# RH007_1.net
KiCad netlist of a schematic drawn in EAGLE
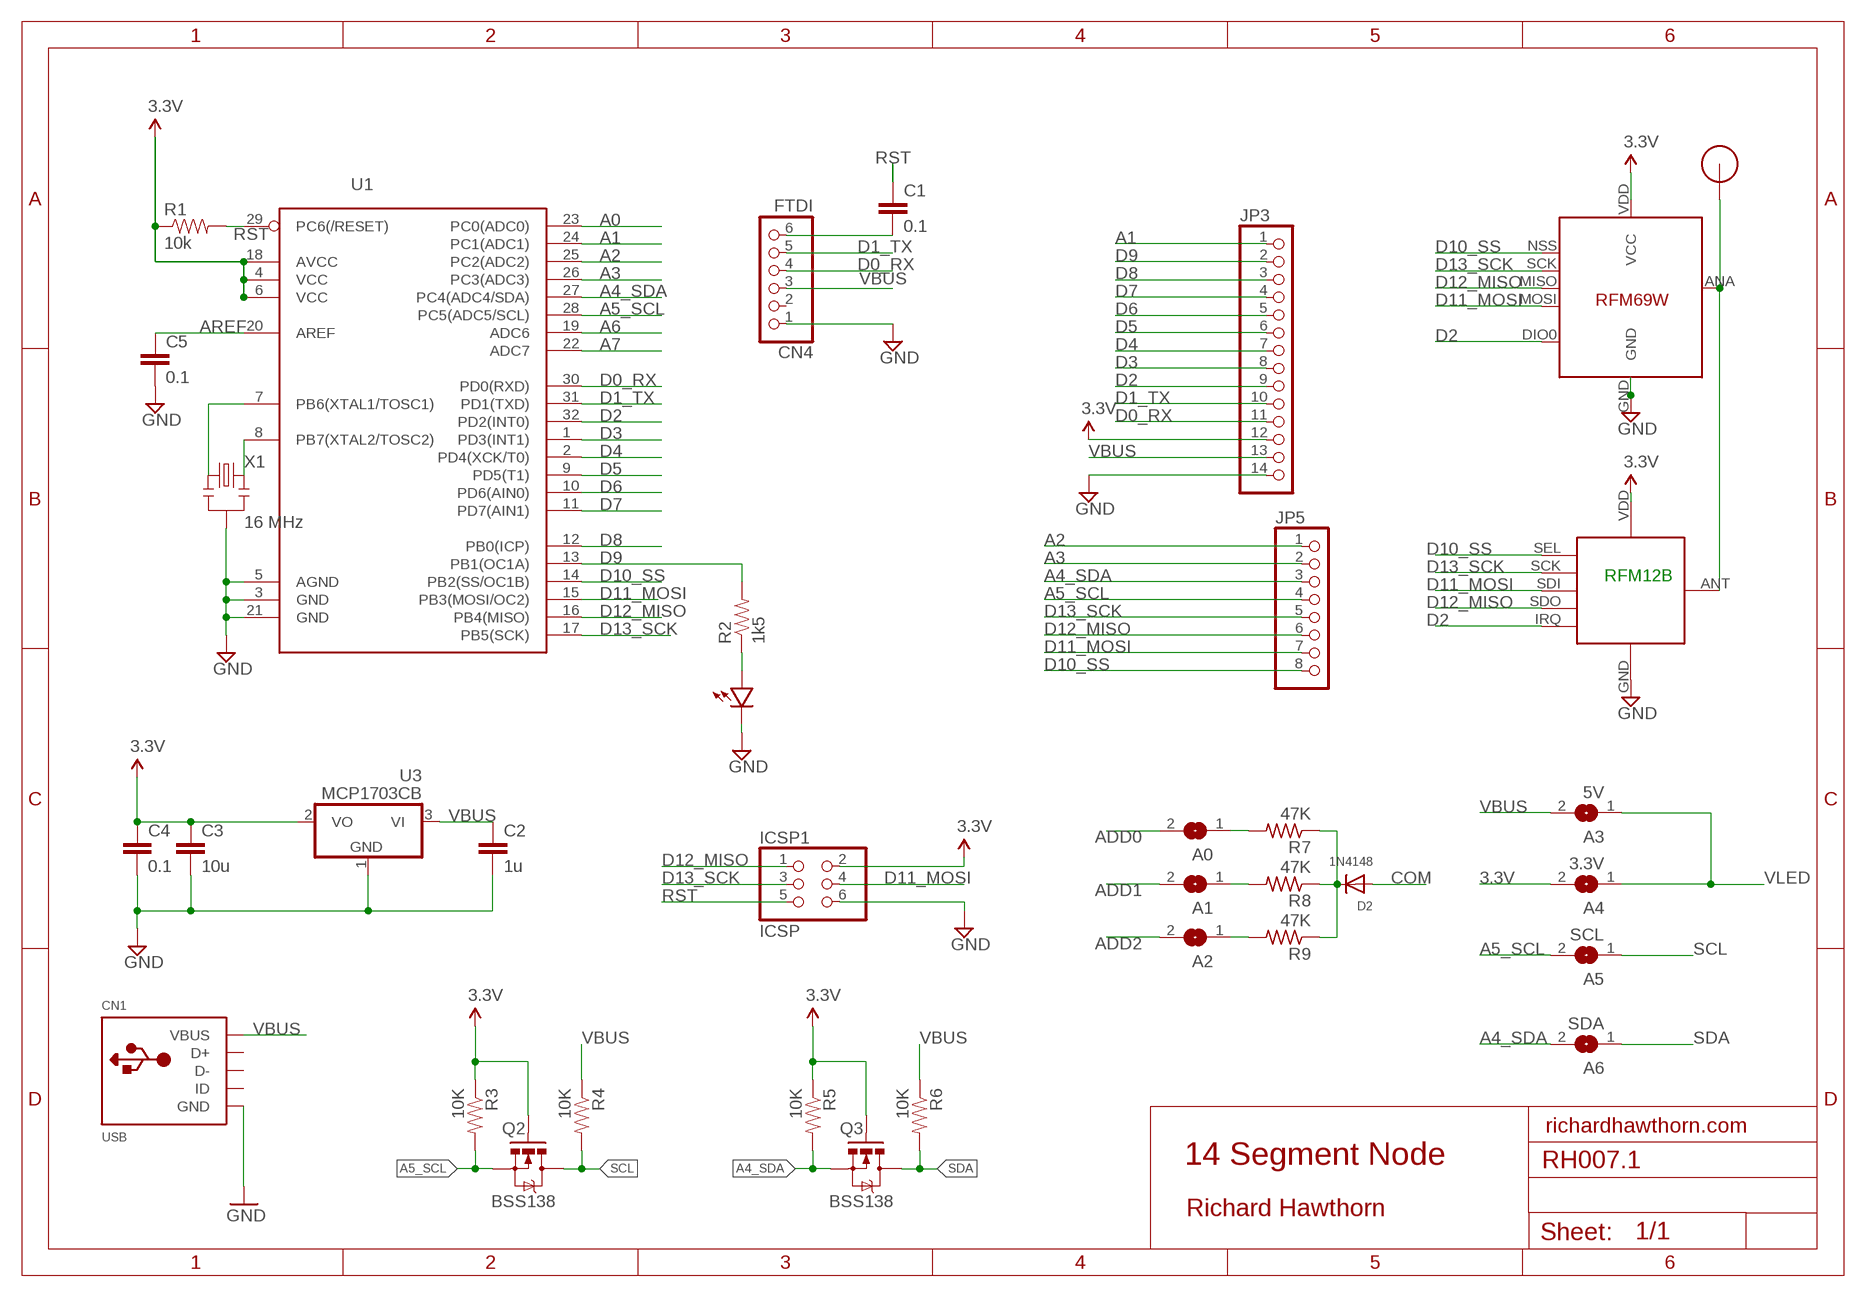
[diagram p0: schematic, sheet 1, part 1 of 2]
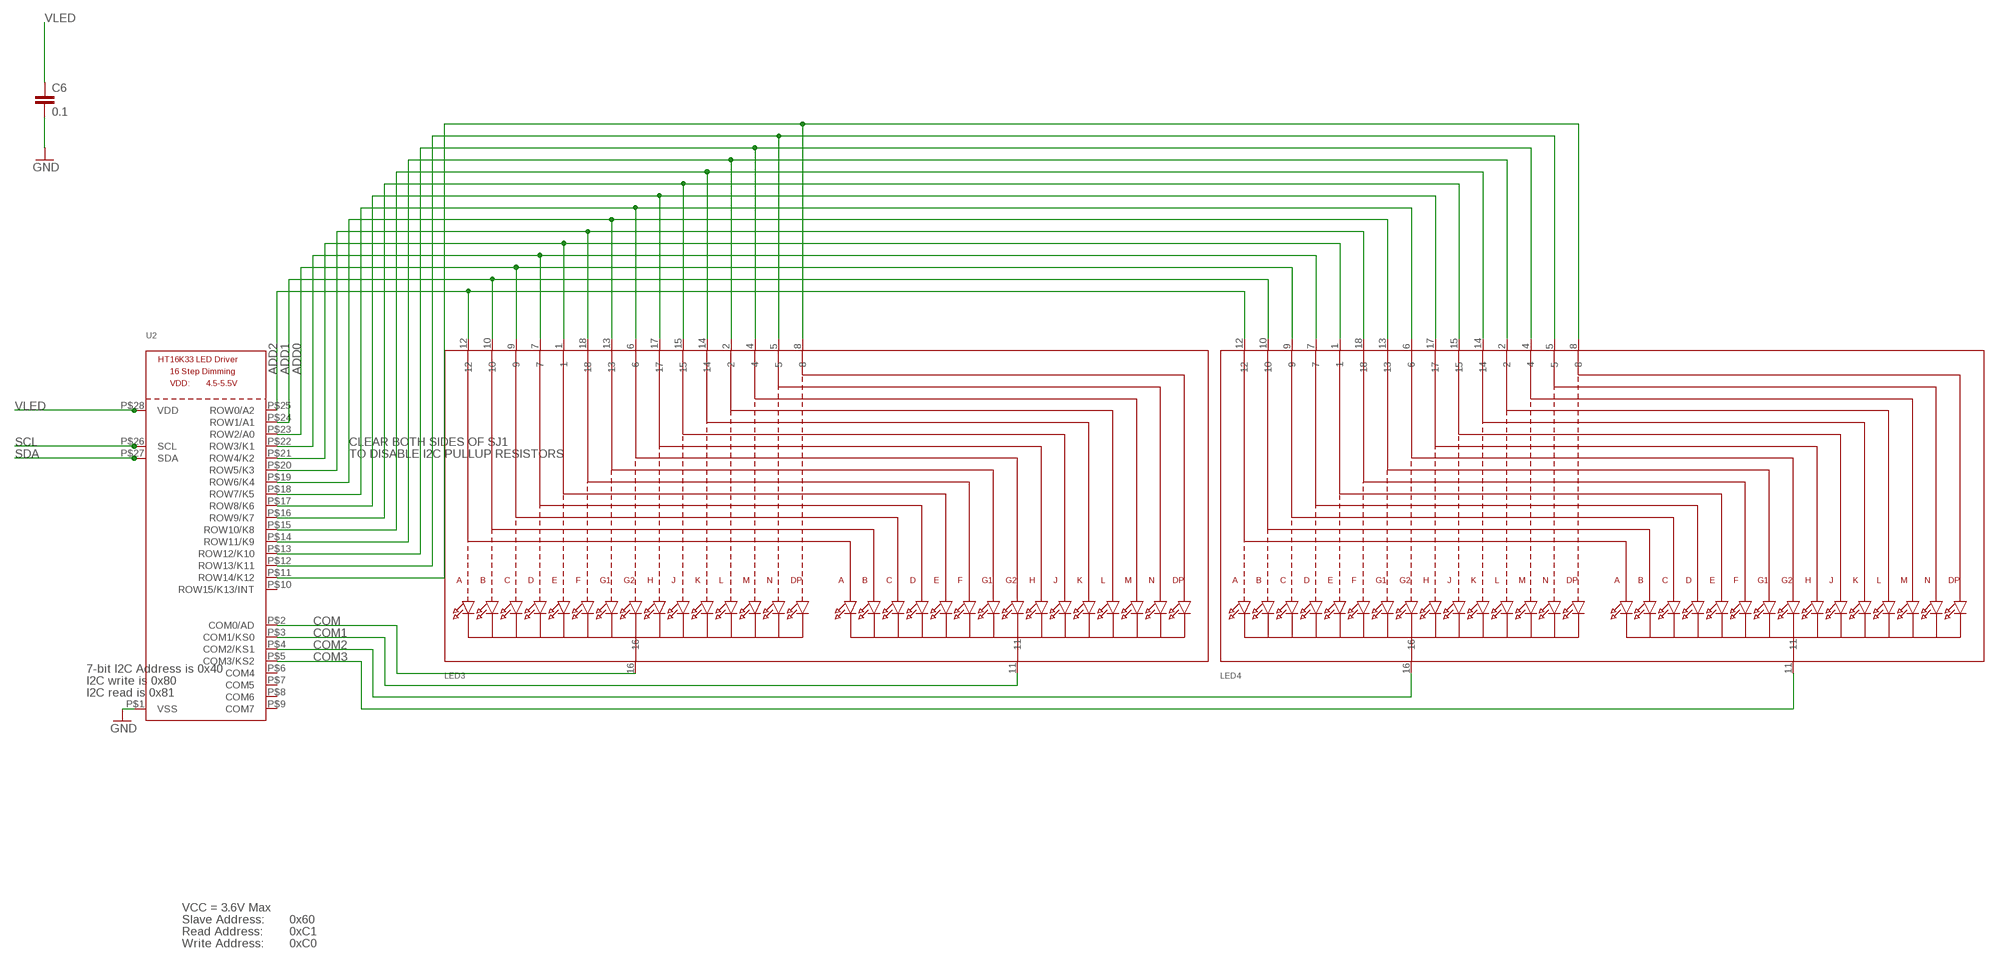
[diagram p1: schematic, sheet 1, part 2 of 2]

(export (version "E")
  (design (tool "Eeschema 10.0.6"))
  (components
    (comp (ref "A0")
      (value "SOLDERJUMPERREFLOW_NOPASTE")
      (footprint "eagle-import:SOLDERJUMPER_REFLOW_NOPASTE")
      (libsource (lib "eagle-import") (part "SOLDERJUMPERREFLOW_NOPASTE"))
    )
    (comp (ref "A1")
      (value "SOLDERJUMPERREFLOW_NOPASTE")
      (footprint "eagle-import:SOLDERJUMPER_REFLOW_NOPASTE")
      (libsource (lib "eagle-import") (part "SOLDERJUMPERREFLOW_NOPASTE"))
    )
    (comp (ref "A2")
      (value "SOLDERJUMPERREFLOW_NOPASTE")
      (footprint "eagle-import:SOLDERJUMPER_REFLOW_NOPASTE")
      (libsource (lib "eagle-import") (part "SOLDERJUMPERREFLOW_NOPASTE"))
    )
    (comp (ref "A3")
      (value "5V")
      (footprint "eagle-import:SOLDERJUMPER_REFLOW_NOPASTE")
      (libsource (lib "eagle-import") (part "SOLDERJUMPERREFLOW_NOPASTE"))
    )
    (comp (ref "A4")
      (value "3.3V")
      (footprint "eagle-import:SOLDERJUMPER_REFLOW_NOPASTE")
      (libsource (lib "eagle-import") (part "SOLDERJUMPERREFLOW_NOPASTE"))
    )
    (comp (ref "A5")
      (value "SCL")
      (footprint "eagle-import:SOLDERJUMPER_REFLOW_NOPASTE")
      (libsource (lib "eagle-import") (part "SOLDERJUMPERREFLOW_NOPASTE"))
    )
    (comp (ref "A6")
      (value "SDA")
      (footprint "eagle-import:SOLDERJUMPER_REFLOW_NOPASTE")
      (libsource (lib "eagle-import") (part "SOLDERJUMPERREFLOW_NOPASTE"))
    )
    (comp (ref "C1")
      (value "0.1")
      (footprint "eagle-import:0603-CAP")
      (libsource (lib "eagle-import") (part "CAP0603-CAP"))
    )
    (comp (ref "C2")
      (value "1u")
      (footprint "eagle-import:0603-CAP")
      (libsource (lib "eagle-import") (part "CAP0603-CAP"))
    )
    (comp (ref "C3")
      (value "10u")
      (footprint "eagle-import:0805-CAP")
      (libsource (lib "eagle-import") (part "CAP0805-CAP"))
    )
    (comp (ref "C4")
      (value "0.1")
      (footprint "eagle-import:0603-CAP")
      (libsource (lib "eagle-import") (part "CAP0603-CAP"))
    )
    (comp (ref "C5")
      (value "0.1")
      (footprint "eagle-import:0603-CAP")
      (libsource (lib "eagle-import") (part "CAP0603-CAP"))
    )
    (comp (ref "C6")
      (value "0.1")
      (footprint "eagle-import:0603-CAP")
      (libsource (lib "eagle-import") (part "CAP0603-CAP"))
    )
    (comp (ref "CN1")
      (value "USB")
      (footprint "eagle-import:USB-MINIB")
      (libsource (lib "eagle-import") (part "USBMINIB"))
    )
    (comp (ref "CN4")
      (value "FTDI")
      (footprint "eagle-import:1X06")
      (libsource (lib "eagle-import") (part "PINHD-1X6"))
    )
    (comp (ref "D2")
      (value "1N4148")
      (footprint "eagle-import:SOD-323F")
      (libsource (lib "eagle-import") (part "DIODESOD-323F"))
    )
    (comp (ref "ICSP1")
      (value "ICSP")
      (footprint "eagle-import:2X03")
      (libsource (lib "eagle-import") (part "PINHD-2X3"))
    )
    (comp (ref "JP3")
      (value "PINHD-1X14")
      (footprint "eagle-import:1X14")
      (libsource (lib "eagle-import") (part "PINHD-1X14"))
    )
    (comp (ref "JP5")
      (value "PINHD-1X8")
      (footprint "eagle-import:1X08")
      (libsource (lib "eagle-import") (part "PINHD-1X8"))
    )
    (comp (ref "LED1")
      (value "LED0603")
      (footprint "eagle-import:0603-LED")
      (libsource (lib "eagle-import") (part "LED0603"))
    )
    (comp (ref "LED3")
      (value "DISP_SEGMENT_STARBURST_DUAL_COMMONCATHODE")
      (footprint "eagle-import:SEGMENT_STARTBUST_DUAL_KWA-541CBB")
      (libsource (lib "eagle-import") (part "DISP_SEGMENT_STARBURST_DUAL_COMMONCATHODE"))
    )
    (comp (ref "LED4")
      (value "DISP_SEGMENT_STARBURST_DUAL_COMMONCATHODE")
      (footprint "eagle-import:SEGMENT_STARTBUST_DUAL_KWA-541CBB")
      (libsource (lib "eagle-import") (part "DISP_SEGMENT_STARBURST_DUAL_COMMONCATHODE"))
    )
    (comp (ref "Q2")
      (value "BSS138")
      (footprint "eagle-import:SOT23-3")
      (libsource (lib "eagle-import") (part "MOSFET-NCHANNELSMD"))
    )
    (comp (ref "Q3")
      (value "BSS138")
      (footprint "eagle-import:SOT23-3")
      (libsource (lib "eagle-import") (part "MOSFET-NCHANNELSMD"))
    )
    (comp (ref "R1")
      (value "10k")
      (footprint "eagle-import:0603-RES")
      (libsource (lib "eagle-import") (part "RESISTOR0603-RES"))
    )
    (comp (ref "R2")
      (value "1k5")
      (footprint "eagle-import:0805")
      (libsource (lib "eagle-import") (part "RESISTOR0805"))
    )
    (comp (ref "R3")
      (value "10K")
      (footprint "eagle-import:0603-RES")
      (libsource (lib "eagle-import") (part "SparkFun_RESISTOR0603-RES"))
    )
    (comp (ref "R4")
      (value "10K")
      (footprint "eagle-import:0603-RES")
      (libsource (lib "eagle-import") (part "SparkFun_RESISTOR0603-RES"))
    )
    (comp (ref "R5")
      (value "10K")
      (footprint "eagle-import:0603-RES")
      (libsource (lib "eagle-import") (part "SparkFun_RESISTOR0603-RES"))
    )
    (comp (ref "R6")
      (value "10K")
      (footprint "eagle-import:0603-RES")
      (libsource (lib "eagle-import") (part "SparkFun_RESISTOR0603-RES"))
    )
    (comp (ref "R7")
      (value "47K")
      (footprint "eagle-import:R0805")
      (libsource (lib "eagle-import") (part "R-US_R0805"))
    )
    (comp (ref "R8")
      (value "47K")
      (footprint "eagle-import:R0805")
      (libsource (lib "eagle-import") (part "R-US_R0805"))
    )
    (comp (ref "R9")
      (value "47K")
      (footprint "eagle-import:R0805")
      (libsource (lib "eagle-import") (part "R-US_R0805"))
    )
    (comp (ref "RF1")
      (value "RFM12B")
      (footprint "eagle-import:RFM12B-MINPADS")
      (libsource (lib "eagle-import") (part "RFM12B_MINPADS"))
    )
    (comp (ref "RF2")
      (value "RFM69")
      (footprint "eagle-import:RFM69W-MINPADS")
      (libsource (lib "eagle-import") (part "RFM69"))
    )
    (comp (ref "U$1")
      (value "RFM12B_ANTENNA")
      (footprint "eagle-import:RFM12B-ANTENNA")
      (libsource (lib "eagle-import") (part "RFM12B_ANTENNA"))
    )
    (comp (ref "U1")
      (value "ATMega-328")
      (footprint "eagle-import:TQFP32-08")
      (libsource (lib "eagle-import") (part "ATMEGA168/328TQFP32"))
    )
    (comp (ref "U2")
      (value "HT16K33_SOP28")
      (footprint "eagle-import:SOP28_300MIL")
      (libsource (lib "eagle-import") (part "HT16K33_SOP28"))
    )
    (comp (ref "U3")
      (value "MCP1703CB")
      (footprint "eagle-import:SOT23")
      (libsource (lib "eagle-import") (part "MCP1703CB"))
    )
    (comp (ref "X1")
      (value "16 MHz")
      (footprint "eagle-import:RESONATOR-SMD")
      (libsource (lib "eagle-import") (part "RESONATORSMD"))
    )
  )
  (nets
    (net (code "1") (name "/A0") (class "Default")
      (node (ref "U1") (pin "23") (pinfunction "PC0(ADC0)_23") (pintype "bidirectional"))
    )
    (net (code "2") (name "/A1") (class "Default")
      (node (ref "JP3") (pin "1") (pinfunction "1_1") (pintype "passive"))
      (node (ref "U1") (pin "24") (pinfunction "PC1(ADC1)_24") (pintype "bidirectional"))
    )
    (net (code "3") (name "/A2") (class "Default")
      (node (ref "JP5") (pin "1") (pinfunction "1_1") (pintype "passive"))
      (node (ref "U1") (pin "25") (pinfunction "PC2(ADC2)_25") (pintype "bidirectional"))
    )
    (net (code "4") (name "/A3") (class "Default")
      (node (ref "JP5") (pin "2") (pinfunction "2_2") (pintype "passive"))
      (node (ref "U1") (pin "26") (pinfunction "PC3(ADC3)_26") (pintype "bidirectional"))
    )
    (net (code "5") (name "/A6") (class "Default")
      (node (ref "U1") (pin "19") (pinfunction "ADC6_19") (pintype "bidirectional"))
    )
    (net (code "6") (name "/A7") (class "Default")
      (node (ref "U1") (pin "22") (pinfunction "ADC7_22") (pintype "bidirectional"))
    )
    (net (code "7") (name "/ADD0") (class "Default")
      (node (ref "A0") (pin "2") (pinfunction "2_2") (pintype "passive"))
      (node (ref "LED3") (pin "9") (pinfunction "9_9") (pintype "bidirectional"))
      (node (ref "LED4") (pin "9") (pinfunction "9_9") (pintype "bidirectional"))
      (node (ref "U2") (pin "P$23") (pinfunction "ROW2/A0_P$23") (pintype "bidirectional"))
    )
    (net (code "8") (name "/ADD1") (class "Default")
      (node (ref "A1") (pin "2") (pinfunction "2_2") (pintype "passive"))
      (node (ref "LED3") (pin "10") (pinfunction "10_10") (pintype "bidirectional"))
      (node (ref "LED4") (pin "10") (pinfunction "10_10") (pintype "bidirectional"))
      (node (ref "U2") (pin "P$24") (pinfunction "ROW1/A1_P$24") (pintype "bidirectional"))
    )
    (net (code "9") (name "/ADD2") (class "Default")
      (node (ref "A2") (pin "2") (pinfunction "2_2") (pintype "passive"))
      (node (ref "LED3") (pin "12") (pinfunction "12_12") (pintype "bidirectional"))
      (node (ref "LED4") (pin "12") (pinfunction "12_12") (pintype "bidirectional"))
      (node (ref "U2") (pin "P$25") (pinfunction "ROW0/A2_P$25") (pintype "bidirectional"))
    )
    (net (code "10") (name "/AREF") (class "Default")
      (node (ref "C5") (pin "1") (pinfunction "1_1") (pintype "passive"))
      (node (ref "U1") (pin "20") (pinfunction "AREF_20") (pintype "bidirectional"))
    )
    (net (code "11") (name "/COM") (class "Default")
      (node (ref "D2") (pin "A") (pinfunction "A_A") (pintype "passive"))
      (node (ref "LED3") (pin "16") (pinfunction "16_16") (pintype "bidirectional"))
      (node (ref "U2") (pin "P$2") (pinfunction "COM0/AD_P$2") (pintype "bidirectional"))
    )
    (net (code "12") (name "/COM1") (class "Default")
      (node (ref "LED3") (pin "11") (pinfunction "11_11") (pintype "bidirectional"))
      (node (ref "U2") (pin "P$3") (pinfunction "COM1/KS0_P$3") (pintype "bidirectional"))
    )
    (net (code "13") (name "/COM2") (class "Default")
      (node (ref "LED4") (pin "16") (pinfunction "16_16") (pintype "bidirectional"))
      (node (ref "U2") (pin "P$4") (pinfunction "COM2/KS1_P$4") (pintype "bidirectional"))
    )
    (net (code "14") (name "/COM3") (class "Default")
      (node (ref "LED4") (pin "11") (pinfunction "11_11") (pintype "bidirectional"))
      (node (ref "U2") (pin "P$5") (pinfunction "COM3/KS2_P$5") (pintype "bidirectional"))
    )
    (net (code "15") (name "/D0_RX") (class "Default")
      (node (ref "CN4") (pin "4") (pinfunction "4_4") (pintype "passive"))
      (node (ref "JP3") (pin "11") (pinfunction "11_11") (pintype "passive"))
      (node (ref "U1") (pin "30") (pinfunction "PD0(RXD)_30") (pintype "bidirectional"))
    )
    (net (code "16") (name "/D1_TX") (class "Default")
      (node (ref "CN4") (pin "5") (pinfunction "5_5") (pintype "passive"))
      (node (ref "JP3") (pin "10") (pinfunction "10_10") (pintype "passive"))
      (node (ref "U1") (pin "31") (pinfunction "PD1(TXD)_31") (pintype "bidirectional"))
    )
    (net (code "17") (name "/D2") (class "Default")
      (node (ref "JP3") (pin "9") (pinfunction "9_9") (pintype "passive"))
      (node (ref "RF1") (pin "IRQ") (pinfunction "IRQ_IRQ") (pintype "bidirectional"))
      (node (ref "RF2") (pin "DIO0") (pinfunction "DIO0_DIO0") (pintype "open_collector"))
      (node (ref "U1") (pin "32") (pinfunction "PD2(INT0)_32") (pintype "bidirectional"))
    )
    (net (code "18") (name "/D3") (class "Default")
      (node (ref "JP3") (pin "8") (pinfunction "8_8") (pintype "passive"))
      (node (ref "U1") (pin "1") (pinfunction "PD3(INT1)_1") (pintype "bidirectional"))
    )
    (net (code "19") (name "/D4") (class "Default")
      (node (ref "JP3") (pin "7") (pinfunction "7_7") (pintype "passive"))
      (node (ref "U1") (pin "2") (pinfunction "PD4(XCK/T0)_2") (pintype "bidirectional"))
    )
    (net (code "20") (name "/D5") (class "Default")
      (node (ref "JP3") (pin "6") (pinfunction "6_6") (pintype "passive"))
      (node (ref "U1") (pin "9") (pinfunction "PD5(T1)_9") (pintype "bidirectional"))
    )
    (net (code "21") (name "/D6") (class "Default")
      (node (ref "JP3") (pin "5") (pinfunction "5_5") (pintype "passive"))
      (node (ref "U1") (pin "10") (pinfunction "PD6(AIN0)_10") (pintype "bidirectional"))
    )
    (net (code "22") (name "/D7") (class "Default")
      (node (ref "JP3") (pin "4") (pinfunction "4_4") (pintype "passive"))
      (node (ref "U1") (pin "11") (pinfunction "PD7(AIN1)_11") (pintype "bidirectional"))
    )
    (net (code "23") (name "/D8") (class "Default")
      (node (ref "JP3") (pin "3") (pinfunction "3_3") (pintype "passive"))
      (node (ref "U1") (pin "12") (pinfunction "PB0(ICP)_12") (pintype "bidirectional"))
    )
    (net (code "24") (name "/D9") (class "Default")
      (node (ref "JP3") (pin "2") (pinfunction "2_2") (pintype "passive"))
      (node (ref "R2") (pin "2") (pinfunction "2_2") (pintype "passive"))
      (node (ref "U1") (pin "13") (pinfunction "PB1(OC1A)_13") (pintype "bidirectional"))
    )
    (net (code "25") (name "/D10_SS") (class "Default")
      (node (ref "JP5") (pin "8") (pinfunction "8_8") (pintype "passive"))
      (node (ref "RF1") (pin "SEL") (pinfunction "SEL_SEL") (pintype "bidirectional"))
      (node (ref "RF2") (pin "NSS") (pinfunction "SEL_NSS") (pintype "input"))
      (node (ref "U1") (pin "14") (pinfunction "PB2(SS/OC1B)_14") (pintype "bidirectional"))
    )
    (net (code "26") (name "/D11_MOSI") (class "Default")
      (node (ref "ICSP1") (pin "4") (pinfunction "4_4") (pintype "passive"))
      (node (ref "JP5") (pin "7") (pinfunction "7_7") (pintype "passive"))
      (node (ref "RF1") (pin "SDI") (pinfunction "SDI/MOSI_SDI") (pintype "bidirectional"))
      (node (ref "RF2") (pin "MOSI") (pinfunction "MOSI_MOSI") (pintype "output"))
      (node (ref "U1") (pin "15") (pinfunction "PB3(MOSI/OC2)_15") (pintype "bidirectional"))
    )
    (net (code "27") (name "/D12_MISO") (class "Default")
      (node (ref "ICSP1") (pin "1") (pinfunction "1_1") (pintype "passive"))
      (node (ref "JP5") (pin "6") (pinfunction "6_6") (pintype "passive"))
      (node (ref "RF1") (pin "SDO") (pinfunction "SDO/MISO_SDO") (pintype "bidirectional"))
      (node (ref "RF2") (pin "MISO") (pinfunction "MISO_MISO") (pintype "input"))
      (node (ref "U1") (pin "16") (pinfunction "PB4(MISO)_16") (pintype "bidirectional"))
    )
    (net (code "28") (name "/D13_SCK") (class "Default")
      (node (ref "ICSP1") (pin "3") (pinfunction "3_3") (pintype "passive"))
      (node (ref "JP5") (pin "5") (pinfunction "5_5") (pintype "passive"))
      (node (ref "RF1") (pin "SCK") (pinfunction "SCK_SCK") (pintype "bidirectional"))
      (node (ref "RF2") (pin "SCK") (pinfunction "SCK_SCK") (pintype "input"))
      (node (ref "U1") (pin "17") (pinfunction "PB5(SCK)_17") (pintype "bidirectional"))
    )
    (net (code "29") (name "/RST") (class "Default")
      (node (ref "C1") (pin "1") (pinfunction "1_1") (pintype "passive"))
      (node (ref "ICSP1") (pin "5") (pinfunction "5_5") (pintype "passive"))
      (node (ref "R1") (pin "2") (pinfunction "2_2") (pintype "passive"))
      (node (ref "U1") (pin "29") (pinfunction "PC6(/RESET)_29") (pintype "bidirectional"))
    )
    (net (code "30") (name "/VBUS") (class "Default")
      (node (ref "A3") (pin "2") (pinfunction "2_2") (pintype "passive"))
      (node (ref "C2") (pin "1") (pinfunction "1_1") (pintype "passive"))
      (node (ref "CN1") (pin "VBUS") (pinfunction "VBUS_VBUS") (pintype "power_in"))
      (node (ref "CN4") (pin "3") (pinfunction "3_3") (pintype "passive"))
      (node (ref "JP3") (pin "13") (pinfunction "13_13") (pintype "passive"))
      (node (ref "R4") (pin "1") (pinfunction "1_1") (pintype "passive"))
      (node (ref "R6") (pin "1") (pinfunction "1_1") (pintype "passive"))
      (node (ref "U3") (pin "3") (pinfunction "VI_3") (pintype "input"))
    )
    (net (code "31") (name "/VLED") (class "Default")
      (node (ref "A3") (pin "1") (pinfunction "1_1") (pintype "passive"))
      (node (ref "A4") (pin "1") (pinfunction "1_1") (pintype "passive"))
      (node (ref "C6") (pin "1") (pinfunction "1_1") (pintype "passive"))
      (node (ref "U2") (pin "P$28") (pinfunction "VDD_P$28") (pintype "bidirectional"))
    )
    (net (code "32") (name "3.3V") (class "Default")
      (node (ref "A4") (pin "2") (pinfunction "2_2") (pintype "passive"))
      (node (ref "C3") (pin "1") (pinfunction "1_1") (pintype "passive"))
      (node (ref "C4") (pin "1") (pinfunction "1_1") (pintype "passive"))
      (node (ref "ICSP1") (pin "2") (pinfunction "2_2") (pintype "passive"))
      (node (ref "JP3") (pin "12") (pinfunction "12_12") (pintype "passive"))
      (node (ref "Q2") (pin "1") (pinfunction "G_1") (pintype "passive"))
      (node (ref "Q3") (pin "1") (pinfunction "G_1") (pintype "passive"))
      (node (ref "R1") (pin "1") (pinfunction "1_1") (pintype "passive"))
      (node (ref "R3") (pin "1") (pinfunction "1_1") (pintype "passive"))
      (node (ref "R5") (pin "1") (pinfunction "1_1") (pintype "passive"))
      (node (ref "RF1") (pin "VDD") (pinfunction "VDD_VDD") (pintype "bidirectional"))
      (node (ref "RF2") (pin "VDD") (pinfunction "VCC_VDD") (pintype "power_in"))
      (node (ref "U1") (pin "18") (pinfunction "AVCC_18") (pintype "bidirectional"))
      (node (ref "U1") (pin "4") (pinfunction "VCC_4") (pintype "bidirectional"))
      (node (ref "U1") (pin "6") (pinfunction "VCC_6") (pintype "bidirectional"))
      (node (ref "U3") (pin "2") (pinfunction "VO_2") (pintype "passive"))
    )
    (net (code "33") (name "A4_SDA") (class "Default")
      (node (ref "A6") (pin "2") (pinfunction "2_2") (pintype "passive"))
      (node (ref "JP5") (pin "3") (pinfunction "3_3") (pintype "passive"))
      (node (ref "Q3") (pin "2") (pinfunction "S_2") (pintype "passive"))
      (node (ref "R5") (pin "2") (pinfunction "2_2") (pintype "passive"))
      (node (ref "U1") (pin "27") (pinfunction "PC4(ADC4/SDA)_27") (pintype "bidirectional"))
    )
    (net (code "34") (name "A5_SCL") (class "Default")
      (node (ref "A5") (pin "2") (pinfunction "2_2") (pintype "passive"))
      (node (ref "JP5") (pin "4") (pinfunction "4_4") (pintype "passive"))
      (node (ref "Q2") (pin "2") (pinfunction "S_2") (pintype "passive"))
      (node (ref "R3") (pin "2") (pinfunction "2_2") (pintype "passive"))
      (node (ref "U1") (pin "28") (pinfunction "PC5(ADC5/SCL)_28") (pintype "bidirectional"))
    )
    (net (code "35") (name "GND") (class "Default")
      (node (ref "C2") (pin "2") (pinfunction "2_2") (pintype "passive"))
      (node (ref "C3") (pin "2") (pinfunction "2_2") (pintype "passive"))
      (node (ref "C4") (pin "2") (pinfunction "2_2") (pintype "passive"))
      (node (ref "C5") (pin "2") (pinfunction "2_2") (pintype "passive"))
      (node (ref "C6") (pin "2") (pinfunction "2_2") (pintype "passive"))
      (node (ref "CN1") (pin "GND") (pinfunction "GND_GND") (pintype "power_in"))
      (node (ref "CN4") (pin "1") (pinfunction "1_1") (pintype "passive"))
      (node (ref "ICSP1") (pin "6") (pinfunction "6_6") (pintype "passive"))
      (node (ref "JP3") (pin "14") (pinfunction "14_14") (pintype "passive"))
      (node (ref "LED1") (pin "MINUS") (pinfunction "MINUS_MINUS") (pintype "passive"))
      (node (ref "RF1") (pin "GND") (pinfunction "GND_GND") (pintype "bidirectional"))
      (node (ref "RF2") (pin "GND") (pinfunction "GND_GND") (pintype "power_in"))
      (node (ref "U1") (pin "21") (pinfunction "GND_21") (pintype "bidirectional"))
      (node (ref "U1") (pin "3") (pinfunction "GND_3") (pintype "bidirectional"))
      (node (ref "U1") (pin "5") (pinfunction "AGND_5") (pintype "bidirectional"))
      (node (ref "U2") (pin "P$1") (pinfunction "VSS_P$1") (pintype "bidirectional"))
      (node (ref "U3") (pin "1") (pinfunction "GND_1") (pintype "passive"))
      (node (ref "X1") (pin "2") (pinfunction "2_2") (pintype "passive"))
    )
    (net (code "36") (name "Net-(A0-Pad1)") (class "Default")
      (node (ref "A0") (pin "1") (pinfunction "1_1") (pintype "passive"))
      (node (ref "R7") (pin "2") (pinfunction "2_2") (pintype "passive"))
    )
    (net (code "37") (name "Net-(A1-Pad1)") (class "Default")
      (node (ref "A1") (pin "1") (pinfunction "1_1") (pintype "passive"))
      (node (ref "R8") (pin "2") (pinfunction "2_2") (pintype "passive"))
    )
    (net (code "38") (name "Net-(A2-Pad1)") (class "Default")
      (node (ref "A2") (pin "1") (pinfunction "1_1") (pintype "passive"))
      (node (ref "R9") (pin "2") (pinfunction "2_2") (pintype "passive"))
    )
    (net (code "39") (name "Net-(C1-Pad2)") (class "Default")
      (node (ref "C1") (pin "2") (pinfunction "2_2") (pintype "passive"))
      (node (ref "CN4") (pin "6") (pinfunction "6_6") (pintype "passive"))
    )
    (net (code "40") (name "Net-(D2-PadC)") (class "Default")
      (node (ref "D2") (pin "C") (pinfunction "C_C") (pintype "passive"))
      (node (ref "R7") (pin "1") (pinfunction "1_1") (pintype "passive"))
      (node (ref "R8") (pin "1") (pinfunction "1_1") (pintype "passive"))
      (node (ref "R9") (pin "1") (pinfunction "1_1") (pintype "passive"))
    )
    (net (code "41") (name "Net-(LED1-PadPLUS)") (class "Default")
      (node (ref "LED1") (pin "PLUS") (pinfunction "PLUS_PLUS") (pintype "passive"))
      (node (ref "R2") (pin "1") (pinfunction "1_1") (pintype "passive"))
    )
    (net (code "42") (name "Net-(RF2-ANT)") (class "Default")
      (node (ref "RF1") (pin "ANT") (pinfunction "ANT_ANT") (pintype "bidirectional"))
      (node (ref "RF2") (pin "ANA") (pinfunction "ANT_ANA") (pintype "passive"))
      (node (ref "U$1") (pin "P$1") (pinfunction "1_P$1") (pintype "bidirectional"))
    )
    (net (code "43") (name "Net-(U1-PB6(XTAL1{slash}TOSC1))") (class "Default")
      (node (ref "U1") (pin "7") (pinfunction "PB6(XTAL1/TOSC1)_7") (pintype "bidirectional"))
      (node (ref "X1") (pin "1") (pinfunction "1_1") (pintype "passive"))
    )
    (net (code "44") (name "Net-(U1-PB7(XTAL2{slash}TOSC2))") (class "Default")
      (node (ref "U1") (pin "8") (pinfunction "PB7(XTAL2/TOSC2)_8") (pintype "bidirectional"))
      (node (ref "X1") (pin "3") (pinfunction "3_3") (pintype "passive"))
    )
    (net (code "45") (name "Net-(U2-ROW3{slash}K1)") (class "Default")
      (node (ref "LED3") (pin "7") (pinfunction "7_7") (pintype "bidirectional"))
      (node (ref "LED4") (pin "7") (pinfunction "7_7") (pintype "bidirectional"))
      (node (ref "U2") (pin "P$22") (pinfunction "ROW3/K1_P$22") (pintype "bidirectional"))
    )
    (net (code "46") (name "Net-(U2-ROW4{slash}K2)") (class "Default")
      (node (ref "LED3") (pin "1") (pinfunction "1_1") (pintype "bidirectional"))
      (node (ref "LED4") (pin "1") (pinfunction "1_1") (pintype "bidirectional"))
      (node (ref "U2") (pin "P$21") (pinfunction "ROW4/K2_P$21") (pintype "bidirectional"))
    )
    (net (code "47") (name "Net-(U2-ROW5{slash}K3)") (class "Default")
      (node (ref "LED3") (pin "18") (pinfunction "18_18") (pintype "bidirectional"))
      (node (ref "LED4") (pin "18") (pinfunction "18_18") (pintype "bidirectional"))
      (node (ref "U2") (pin "P$20") (pinfunction "ROW5/K3_P$20") (pintype "bidirectional"))
    )
    (net (code "48") (name "Net-(U2-ROW6{slash}K4)") (class "Default")
      (node (ref "LED3") (pin "13") (pinfunction "13_13") (pintype "bidirectional"))
      (node (ref "LED4") (pin "13") (pinfunction "13_13") (pintype "bidirectional"))
      (node (ref "U2") (pin "P$19") (pinfunction "ROW6/K4_P$19") (pintype "bidirectional"))
    )
    (net (code "49") (name "Net-(U2-ROW7{slash}K5)") (class "Default")
      (node (ref "LED3") (pin "6") (pinfunction "6_6") (pintype "bidirectional"))
      (node (ref "LED4") (pin "6") (pinfunction "6_6") (pintype "bidirectional"))
      (node (ref "U2") (pin "P$18") (pinfunction "ROW7/K5_P$18") (pintype "bidirectional"))
    )
    (net (code "50") (name "Net-(U2-ROW8{slash}K6)") (class "Default")
      (node (ref "LED3") (pin "17") (pinfunction "17_17") (pintype "bidirectional"))
      (node (ref "LED4") (pin "17") (pinfunction "17_17") (pintype "bidirectional"))
      (node (ref "U2") (pin "P$17") (pinfunction "ROW8/K6_P$17") (pintype "bidirectional"))
    )
    (net (code "51") (name "Net-(U2-ROW9{slash}K7)") (class "Default")
      (node (ref "LED3") (pin "15") (pinfunction "15_15") (pintype "bidirectional"))
      (node (ref "LED4") (pin "15") (pinfunction "15_15") (pintype "bidirectional"))
      (node (ref "U2") (pin "P$16") (pinfunction "ROW9/K7_P$16") (pintype "bidirectional"))
    )
    (net (code "52") (name "Net-(U2-ROW10{slash}K8)") (class "Default")
      (node (ref "LED3") (pin "14") (pinfunction "14_14") (pintype "bidirectional"))
      (node (ref "LED4") (pin "14") (pinfunction "14_14") (pintype "bidirectional"))
      (node (ref "U2") (pin "P$15") (pinfunction "ROW10/K8_P$15") (pintype "bidirectional"))
    )
    (net (code "53") (name "Net-(U2-ROW11{slash}K9)") (class "Default")
      (node (ref "LED3") (pin "2") (pinfunction "2_2") (pintype "bidirectional"))
      (node (ref "LED4") (pin "2") (pinfunction "2_2") (pintype "bidirectional"))
      (node (ref "U2") (pin "P$14") (pinfunction "ROW11/K9_P$14") (pintype "bidirectional"))
    )
    (net (code "54") (name "Net-(U2-ROW12{slash}K10)") (class "Default")
      (node (ref "LED3") (pin "4") (pinfunction "4_4") (pintype "bidirectional"))
      (node (ref "LED4") (pin "4") (pinfunction "4_4") (pintype "bidirectional"))
      (node (ref "U2") (pin "P$13") (pinfunction "ROW12/K10_P$13") (pintype "bidirectional"))
    )
    (net (code "55") (name "Net-(U2-ROW13{slash}K11)") (class "Default")
      (node (ref "LED3") (pin "5") (pinfunction "5_5") (pintype "bidirectional"))
      (node (ref "LED4") (pin "5") (pinfunction "5_5") (pintype "bidirectional"))
      (node (ref "U2") (pin "P$12") (pinfunction "ROW13/K11_P$12") (pintype "bidirectional"))
    )
    (net (code "56") (name "Net-(U2-ROW14{slash}K12)") (class "Default")
      (node (ref "LED3") (pin "8") (pinfunction "8_8") (pintype "bidirectional"))
      (node (ref "LED4") (pin "8") (pinfunction "8_8") (pintype "bidirectional"))
      (node (ref "U2") (pin "P$11") (pinfunction "ROW14/K12_P$11") (pintype "bidirectional"))
    )
    (net (code "57") (name "SCL") (class "Default")
      (node (ref "A5") (pin "1") (pinfunction "1_1") (pintype "passive"))
      (node (ref "Q2") (pin "3") (pinfunction "D_3") (pintype "passive"))
      (node (ref "R4") (pin "2") (pinfunction "2_2") (pintype "passive"))
      (node (ref "U2") (pin "P$26") (pinfunction "SCL_P$26") (pintype "bidirectional"))
    )
    (net (code "58") (name "SDA") (class "Default")
      (node (ref "A6") (pin "1") (pinfunction "1_1") (pintype "passive"))
      (node (ref "Q3") (pin "3") (pinfunction "D_3") (pintype "passive"))
      (node (ref "R6") (pin "2") (pinfunction "2_2") (pintype "passive"))
      (node (ref "U2") (pin "P$27") (pinfunction "SDA_P$27") (pintype "bidirectional"))
    )
    (net (code "59") (name "unconnected-(CN1-PadD+)") (class "Default")
      (node (ref "CN1") (pin "D+") (pinfunction "D+_D+") (pintype "bidirectional"))
    )
    (net (code "60") (name "unconnected-(CN1-PadD-)") (class "Default")
      (node (ref "CN1") (pin "D-") (pinfunction "D-_D-") (pintype "bidirectional"))
    )
    (net (code "61") (name "unconnected-(CN1-PadID)") (class "Default")
      (node (ref "CN1") (pin "ID") (pinfunction "ID_ID") (pintype "bidirectional"))
    )
    (net (code "62") (name "unconnected-(CN4-Pad2)") (class "Default")
      (node (ref "CN4") (pin "2") (pinfunction "2_2") (pintype "passive"))
    )
    (net (code "63") (name "unconnected-(U2-COM4-PadP$6)") (class "Default")
      (node (ref "U2") (pin "P$6") (pinfunction "COM4_P$6") (pintype "bidirectional"))
    )
    (net (code "64") (name "unconnected-(U2-COM5-PadP$7)") (class "Default")
      (node (ref "U2") (pin "P$7") (pinfunction "COM5_P$7") (pintype "bidirectional"))
    )
    (net (code "65") (name "unconnected-(U2-COM6-PadP$8)") (class "Default")
      (node (ref "U2") (pin "P$8") (pinfunction "COM6_P$8") (pintype "bidirectional"))
    )
    (net (code "66") (name "unconnected-(U2-COM7-PadP$9)") (class "Default")
      (node (ref "U2") (pin "P$9") (pinfunction "COM7_P$9") (pintype "bidirectional"))
    )
    (net (code "67") (name "unconnected-(U2-ROW15{slash}K13{slash}INT-PadP$10)") (class "Default")
      (node (ref "U2") (pin "P$10") (pinfunction "ROW15/K13/INT_P$10") (pintype "bidirectional"))
    )
  )
)
